# Automated_Gardening.net
KiCad netlist of a schematic drawn in EAGLE
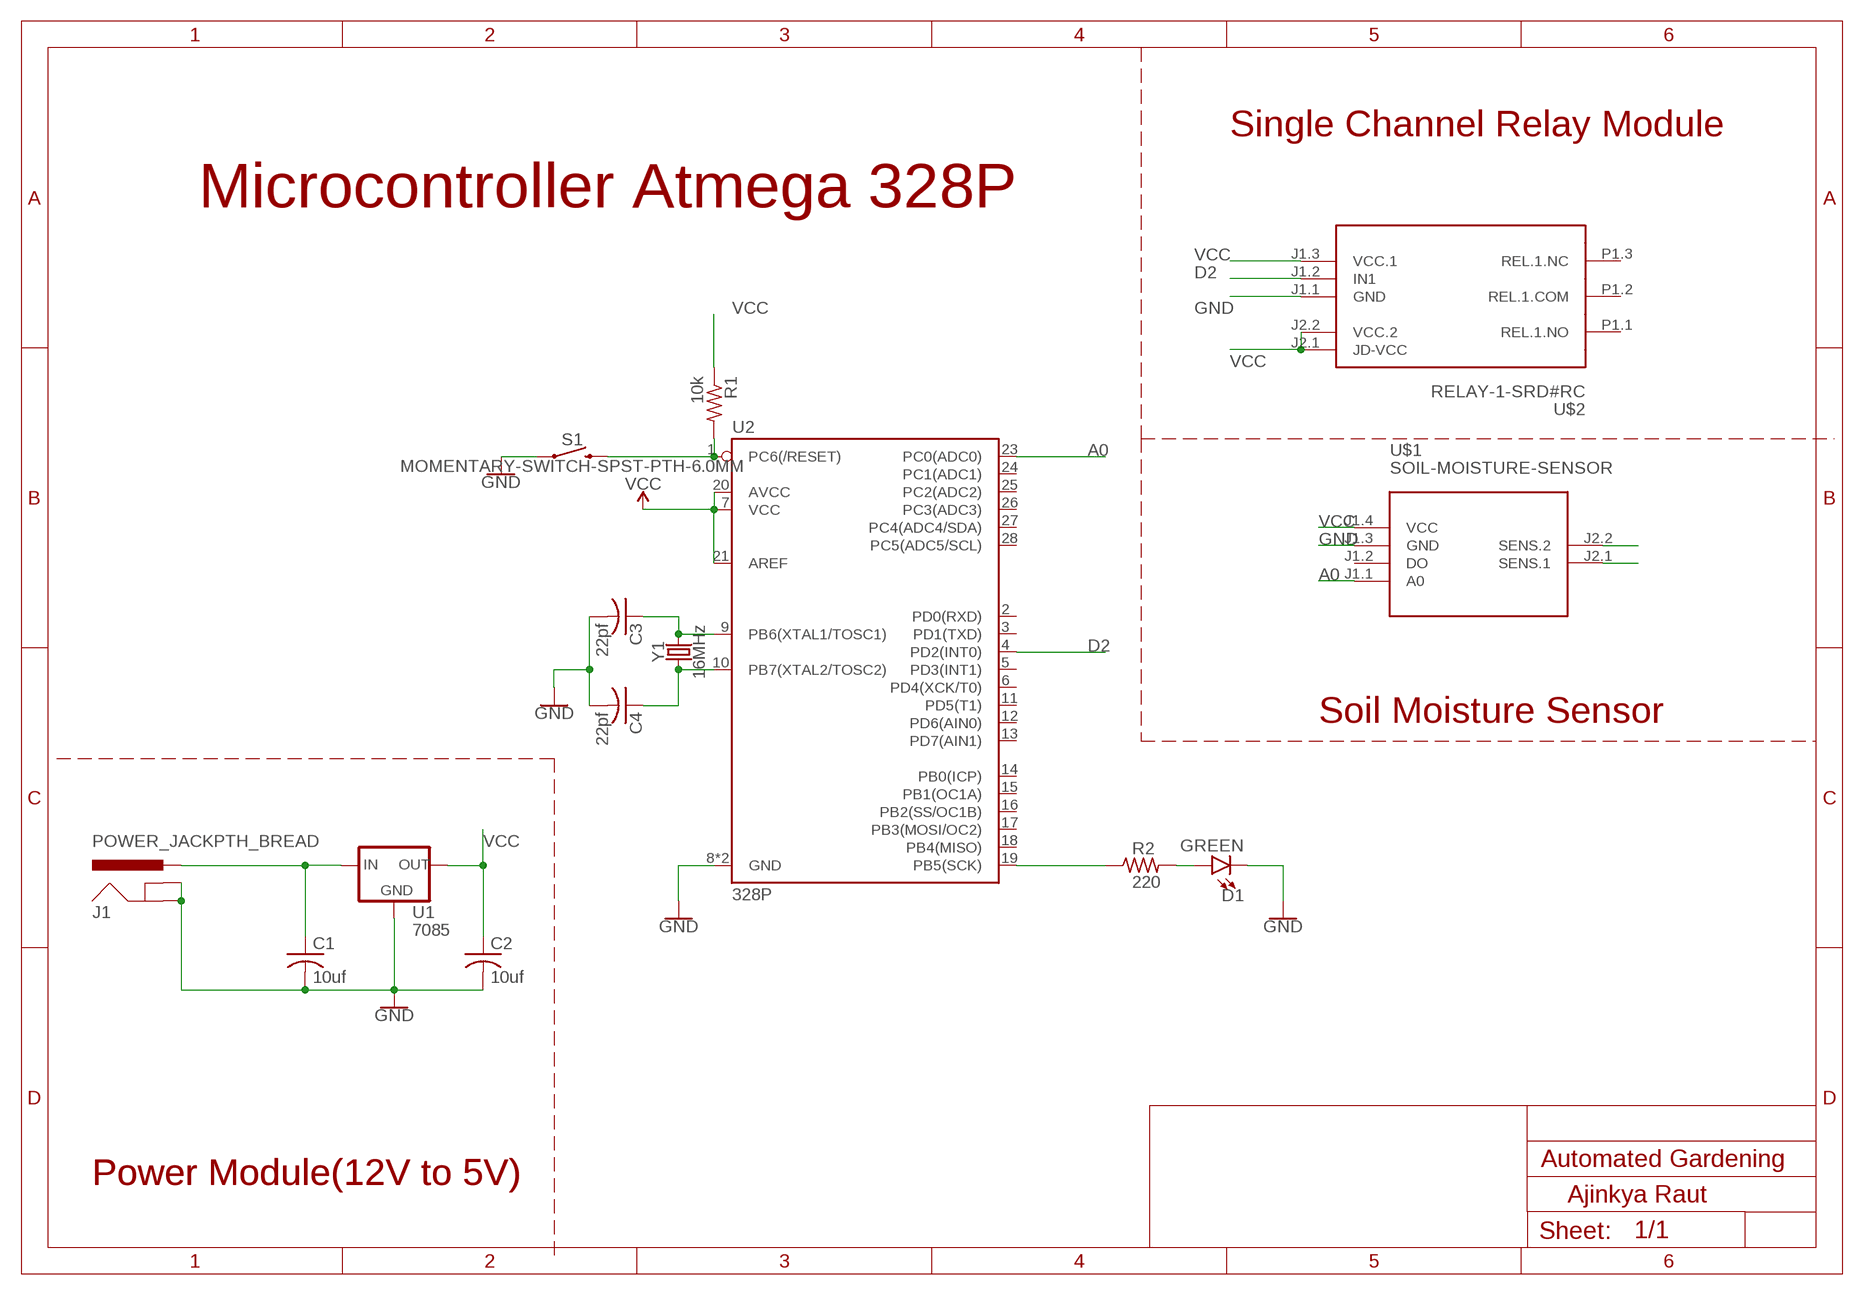
[diagram p0: schematic, sheet 1]

(export (version "E")
  (design (tool "Eeschema 10.0.6"))
  (components
    (comp (ref "C1")
      (value "10uf")
      (footprint "eagle-import:C050-025X075")
      (libsource (lib "eagle-import") (part "C-US050-025X075"))
    )
    (comp (ref "C2")
      (value "10uf")
      (footprint "eagle-import:C050-025X075")
      (libsource (lib "eagle-import") (part "C-US050-025X075"))
    )
    (comp (ref "C3")
      (value "22pf")
      (footprint "eagle-import:C050-050X075")
      (libsource (lib "eagle-import") (part "C-US050-050X075"))
    )
    (comp (ref "C4")
      (value "22pf")
      (footprint "eagle-import:C050-050X075")
      (libsource (lib "eagle-import") (part "C-US050-050X075"))
    )
    (comp (ref "D1")
      (value "GREEN")
      (footprint "eagle-import:LED_5MM")
      (libsource (lib "eagle-import") (part "LED5MM"))
    )
    (comp (ref "J1")
      (value "POWER_JACKPTH_BREAD")
      (footprint "eagle-import:POWER_JACK_PTH_BREAD")
      (libsource (lib "eagle-import") (part "POWER_JACKPTH_BREAD"))
    )
    (comp (ref "R1")
      (value "10k")
      (footprint "eagle-import:0309_12")
      (libsource (lib "eagle-import") (part "R-US_0309/12"))
    )
    (comp (ref "R2")
      (value "220")
      (footprint "eagle-import:0309_12")
      (libsource (lib "eagle-import") (part "R-US_0309/12"))
    )
    (comp (ref "S1")
      (value "MOMENTARY-SWITCH-SPST-PTH-6.0MM")
      (footprint "eagle-import:TACTILE_SWITCH_PTH_6.0MM")
      (libsource (lib "eagle-import") (part "MOMENTARY-SWITCH-SPST-PTH-6.0MM"))
    )
    (comp (ref "U$1")
      (value "SOIL-MOISTURE-SENSOR")
      (footprint "eagle-import:SOIL-MOISTURE-SENSOR")
      (libsource (lib "eagle-import") (part "SOIL-MOISTURE-SENSOR"))
    )
    (comp (ref "U$2")
      (value "RELAY-1-SRD#RC")
      (footprint "eagle-import:RELAY-1-SRD#RC")
      (libsource (lib "eagle-import") (part "RELAY-1-SRD#RC"))
    )
    (comp (ref "U1")
      (value "7085")
      (footprint "eagle-import:TO-220-ALT")
      (libsource (lib "eagle-import") (part "V_REG_78XX-TO-220"))
    )
    (comp (ref "U2")
      (value "328P")
      (footprint "eagle-import:DIP28")
      (libsource (lib "eagle-import") (part "ATMEGA328P_PDIP"))
    )
    (comp (ref "Y1")
      (value "16MHz")
      (footprint "eagle-import:HC49US")
      (libsource (lib "eagle-import") (part "CRYSTAL-16MHZPTH-HC49US"))
    )
  )
  (nets
    (net (code "1") (name "/A0") (class "Default")
      (node (ref "U$1") (pin "J1.1") (pinfunction "A0_J1.1") (pintype "bidirectional"))
      (node (ref "U2") (pin "23") (pinfunction "PC0(ADC0)_23") (pintype "bidirectional"))
    )
    (net (code "2") (name "/D2") (class "Default")
      (node (ref "U$2") (pin "J1.2") (pinfunction "IN1_J1.2") (pintype "bidirectional"))
      (node (ref "U2") (pin "4") (pinfunction "PD2(INT0)_4") (pintype "bidirectional"))
    )
    (net (code "3") (name "GND") (class "Default")
      (node (ref "C1") (pin "2") (pinfunction "2_2") (pintype "passive"))
      (node (ref "C2") (pin "2") (pinfunction "2_2") (pintype "passive"))
      (node (ref "C3") (pin "2") (pinfunction "2_2") (pintype "passive"))
      (node (ref "C4") (pin "2") (pinfunction "2_2") (pintype "passive"))
      (node (ref "D1") (pin "K") (pinfunction "C_K") (pintype "passive"))
      (node (ref "J1") (pin "GND") (pinfunction "GND_GND") (pintype "bidirectional"))
      (node (ref "J1") (pin "GNDBREAK") (pinfunction "GNDBREAK_GNDBREAK") (pintype "bidirectional"))
      (node (ref "S1") (pin "1") (pinfunction "1_1") (pintype "passive"))
      (node (ref "U$1") (pin "J1.3") (pinfunction "GND_J1.3") (pintype "power_in"))
      (node (ref "U$2") (pin "J1.1") (pinfunction "GND_J1.1") (pintype "power_in"))
      (node (ref "U1") (pin "GND") (pinfunction "GND_GND") (pintype "input"))
      (node (ref "U2") (pin "22") (pinfunction "GND_22") (pintype "bidirectional"))
      (node (ref "U2") (pin "8") (pinfunction "GND_8") (pintype "bidirectional"))
    )
    (net (code "4") (name "Net-(C1-Pad1)") (class "Default")
      (node (ref "C1") (pin "1") (pinfunction "1_1") (pintype "passive"))
      (node (ref "J1") (pin "PWR") (pinfunction "PWR_PWR") (pintype "bidirectional"))
      (node (ref "U1") (pin "IN") (pinfunction "IN_IN") (pintype "input"))
    )
    (net (code "5") (name "Net-(D1-PadA)") (class "Default")
      (node (ref "D1") (pin "A") (pinfunction "A_A") (pintype "passive"))
      (node (ref "R2") (pin "2") (pinfunction "2_2") (pintype "passive"))
    )
    (net (code "6") (name "Net-(S1-2)") (class "Default")
      (node (ref "R1") (pin "2") (pinfunction "2_2") (pintype "passive"))
      (node (ref "S1") (pin "3") (pinfunction "2_3") (pintype "passive"))
      (node (ref "U2") (pin "1") (pinfunction "PC6(/RESET)_1") (pintype "bidirectional"))
    )
    (net (code "7") (name "Net-(U2-PB5(SCK))") (class "Default")
      (node (ref "R2") (pin "1") (pinfunction "1_1") (pintype "passive"))
      (node (ref "U2") (pin "19") (pinfunction "PB5(SCK)_19") (pintype "bidirectional"))
    )
    (net (code "8") (name "Net-(U2-PB6(XTAL1{slash}TOSC1))") (class "Default")
      (node (ref "C3") (pin "1") (pinfunction "1_1") (pintype "passive"))
      (node (ref "U2") (pin "9") (pinfunction "PB6(XTAL1/TOSC1)_9") (pintype "bidirectional"))
      (node (ref "Y1") (pin "2") (pinfunction "2_2") (pintype "passive"))
    )
    (net (code "9") (name "Net-(U2-PB7(XTAL2{slash}TOSC2))") (class "Default")
      (node (ref "C4") (pin "1") (pinfunction "1_1") (pintype "passive"))
      (node (ref "U2") (pin "10") (pinfunction "PB7(XTAL2/TOSC2)_10") (pintype "bidirectional"))
      (node (ref "Y1") (pin "1") (pinfunction "1_1") (pintype "passive"))
    )
    (net (code "10") (name "VCC") (class "Default")
      (node (ref "C2") (pin "1") (pinfunction "1_1") (pintype "passive"))
      (node (ref "R1") (pin "1") (pinfunction "1_1") (pintype "passive"))
      (node (ref "U$1") (pin "J1.4") (pinfunction "VCC_J1.4") (pintype "power_in"))
      (node (ref "U$2") (pin "J1.3") (pinfunction "VCC.1_J1.3") (pintype "power_in"))
      (node (ref "U$2") (pin "J2.1") (pinfunction "JD-VCC_J2.1") (pintype "bidirectional"))
      (node (ref "U$2") (pin "J2.2") (pinfunction "VCC.2_J2.2") (pintype "power_in"))
      (node (ref "U1") (pin "OUT") (pinfunction "OUT_OUT") (pintype "passive"))
      (node (ref "U2") (pin "20") (pinfunction "AVCC_20") (pintype "bidirectional"))
      (node (ref "U2") (pin "21") (pinfunction "AREF_21") (pintype "bidirectional"))
      (node (ref "U2") (pin "7") (pinfunction "VCC_7") (pintype "bidirectional"))
    )
    (net (code "11") (name "unconnected-(U$1-DO-PadJ1.2)") (class "Default")
      (node (ref "U$1") (pin "J1.2") (pinfunction "DO_J1.2") (pintype "output"))
    )
    (net (code "12") (name "unconnected-(U$1-SENS.1-PadJ2.1)") (class "Default")
      (node (ref "U$1") (pin "J2.1") (pinfunction "SENS.1_J2.1") (pintype "bidirectional"))
    )
    (net (code "13") (name "unconnected-(U$1-SENS.2-PadJ2.2)") (class "Default")
      (node (ref "U$1") (pin "J2.2") (pinfunction "SENS.2_J2.2") (pintype "bidirectional"))
    )
    (net (code "14") (name "unconnected-(U$2-REL.1.COM-PadP1.2)") (class "Default")
      (node (ref "U$2") (pin "P1.2") (pinfunction "REL.1.COM_P1.2") (pintype "bidirectional"))
    )
    (net (code "15") (name "unconnected-(U$2-REL.1.NC-PadP1.3)") (class "Default")
      (node (ref "U$2") (pin "P1.3") (pinfunction "REL.1.NC_P1.3") (pintype "bidirectional"))
    )
    (net (code "16") (name "unconnected-(U$2-REL.1.NO-PadP1.1)") (class "Default")
      (node (ref "U$2") (pin "P1.1") (pinfunction "REL.1.NO_P1.1") (pintype "bidirectional"))
    )
    (net (code "17") (name "unconnected-(U2-PB0(ICP)-Pad14)") (class "Default")
      (node (ref "U2") (pin "14") (pinfunction "PB0(ICP)_14") (pintype "bidirectional"))
    )
    (net (code "18") (name "unconnected-(U2-PB1(OC1A)-Pad15)") (class "Default")
      (node (ref "U2") (pin "15") (pinfunction "PB1(OC1A)_15") (pintype "bidirectional"))
    )
    (net (code "19") (name "unconnected-(U2-PB2(SS{slash}OC1B)-Pad16)") (class "Default")
      (node (ref "U2") (pin "16") (pinfunction "PB2(SS/OC1B)_16") (pintype "bidirectional"))
    )
    (net (code "20") (name "unconnected-(U2-PB3(MOSI{slash}OC2)-Pad17)") (class "Default")
      (node (ref "U2") (pin "17") (pinfunction "PB3(MOSI/OC2)_17") (pintype "bidirectional"))
    )
    (net (code "21") (name "unconnected-(U2-PB4(MISO)-Pad18)") (class "Default")
      (node (ref "U2") (pin "18") (pinfunction "PB4(MISO)_18") (pintype "bidirectional"))
    )
    (net (code "22") (name "unconnected-(U2-PC1(ADC1)-Pad24)") (class "Default")
      (node (ref "U2") (pin "24") (pinfunction "PC1(ADC1)_24") (pintype "bidirectional"))
    )
    (net (code "23") (name "unconnected-(U2-PC2(ADC2)-Pad25)") (class "Default")
      (node (ref "U2") (pin "25") (pinfunction "PC2(ADC2)_25") (pintype "bidirectional"))
    )
    (net (code "24") (name "unconnected-(U2-PC3(ADC3)-Pad26)") (class "Default")
      (node (ref "U2") (pin "26") (pinfunction "PC3(ADC3)_26") (pintype "bidirectional"))
    )
    (net (code "25") (name "unconnected-(U2-PC4(ADC4{slash}SDA)-Pad27)") (class "Default")
      (node (ref "U2") (pin "27") (pinfunction "PC4(ADC4/SDA)_27") (pintype "bidirectional"))
    )
    (net (code "26") (name "unconnected-(U2-PC5(ADC5{slash}SCL)-Pad28)") (class "Default")
      (node (ref "U2") (pin "28") (pinfunction "PC5(ADC5/SCL)_28") (pintype "bidirectional"))
    )
    (net (code "27") (name "unconnected-(U2-PD0(RXD)-Pad2)") (class "Default")
      (node (ref "U2") (pin "2") (pinfunction "PD0(RXD)_2") (pintype "bidirectional"))
    )
    (net (code "28") (name "unconnected-(U2-PD1(TXD)-Pad3)") (class "Default")
      (node (ref "U2") (pin "3") (pinfunction "PD1(TXD)_3") (pintype "bidirectional"))
    )
    (net (code "29") (name "unconnected-(U2-PD3(INT1)-Pad5)") (class "Default")
      (node (ref "U2") (pin "5") (pinfunction "PD3(INT1)_5") (pintype "bidirectional"))
    )
    (net (code "30") (name "unconnected-(U2-PD4(XCK{slash}T0)-Pad6)") (class "Default")
      (node (ref "U2") (pin "6") (pinfunction "PD4(XCK/T0)_6") (pintype "bidirectional"))
    )
    (net (code "31") (name "unconnected-(U2-PD5(T1)-Pad11)") (class "Default")
      (node (ref "U2") (pin "11") (pinfunction "PD5(T1)_11") (pintype "bidirectional"))
    )
    (net (code "32") (name "unconnected-(U2-PD6(AIN0)-Pad12)") (class "Default")
      (node (ref "U2") (pin "12") (pinfunction "PD6(AIN0)_12") (pintype "bidirectional"))
    )
    (net (code "33") (name "unconnected-(U2-PD7(AIN1)-Pad13)") (class "Default")
      (node (ref "U2") (pin "13") (pinfunction "PD7(AIN1)_13") (pintype "bidirectional"))
    )
  )
)
